# v2.net
KiCad netlist of a schematic drawn in EAGLE
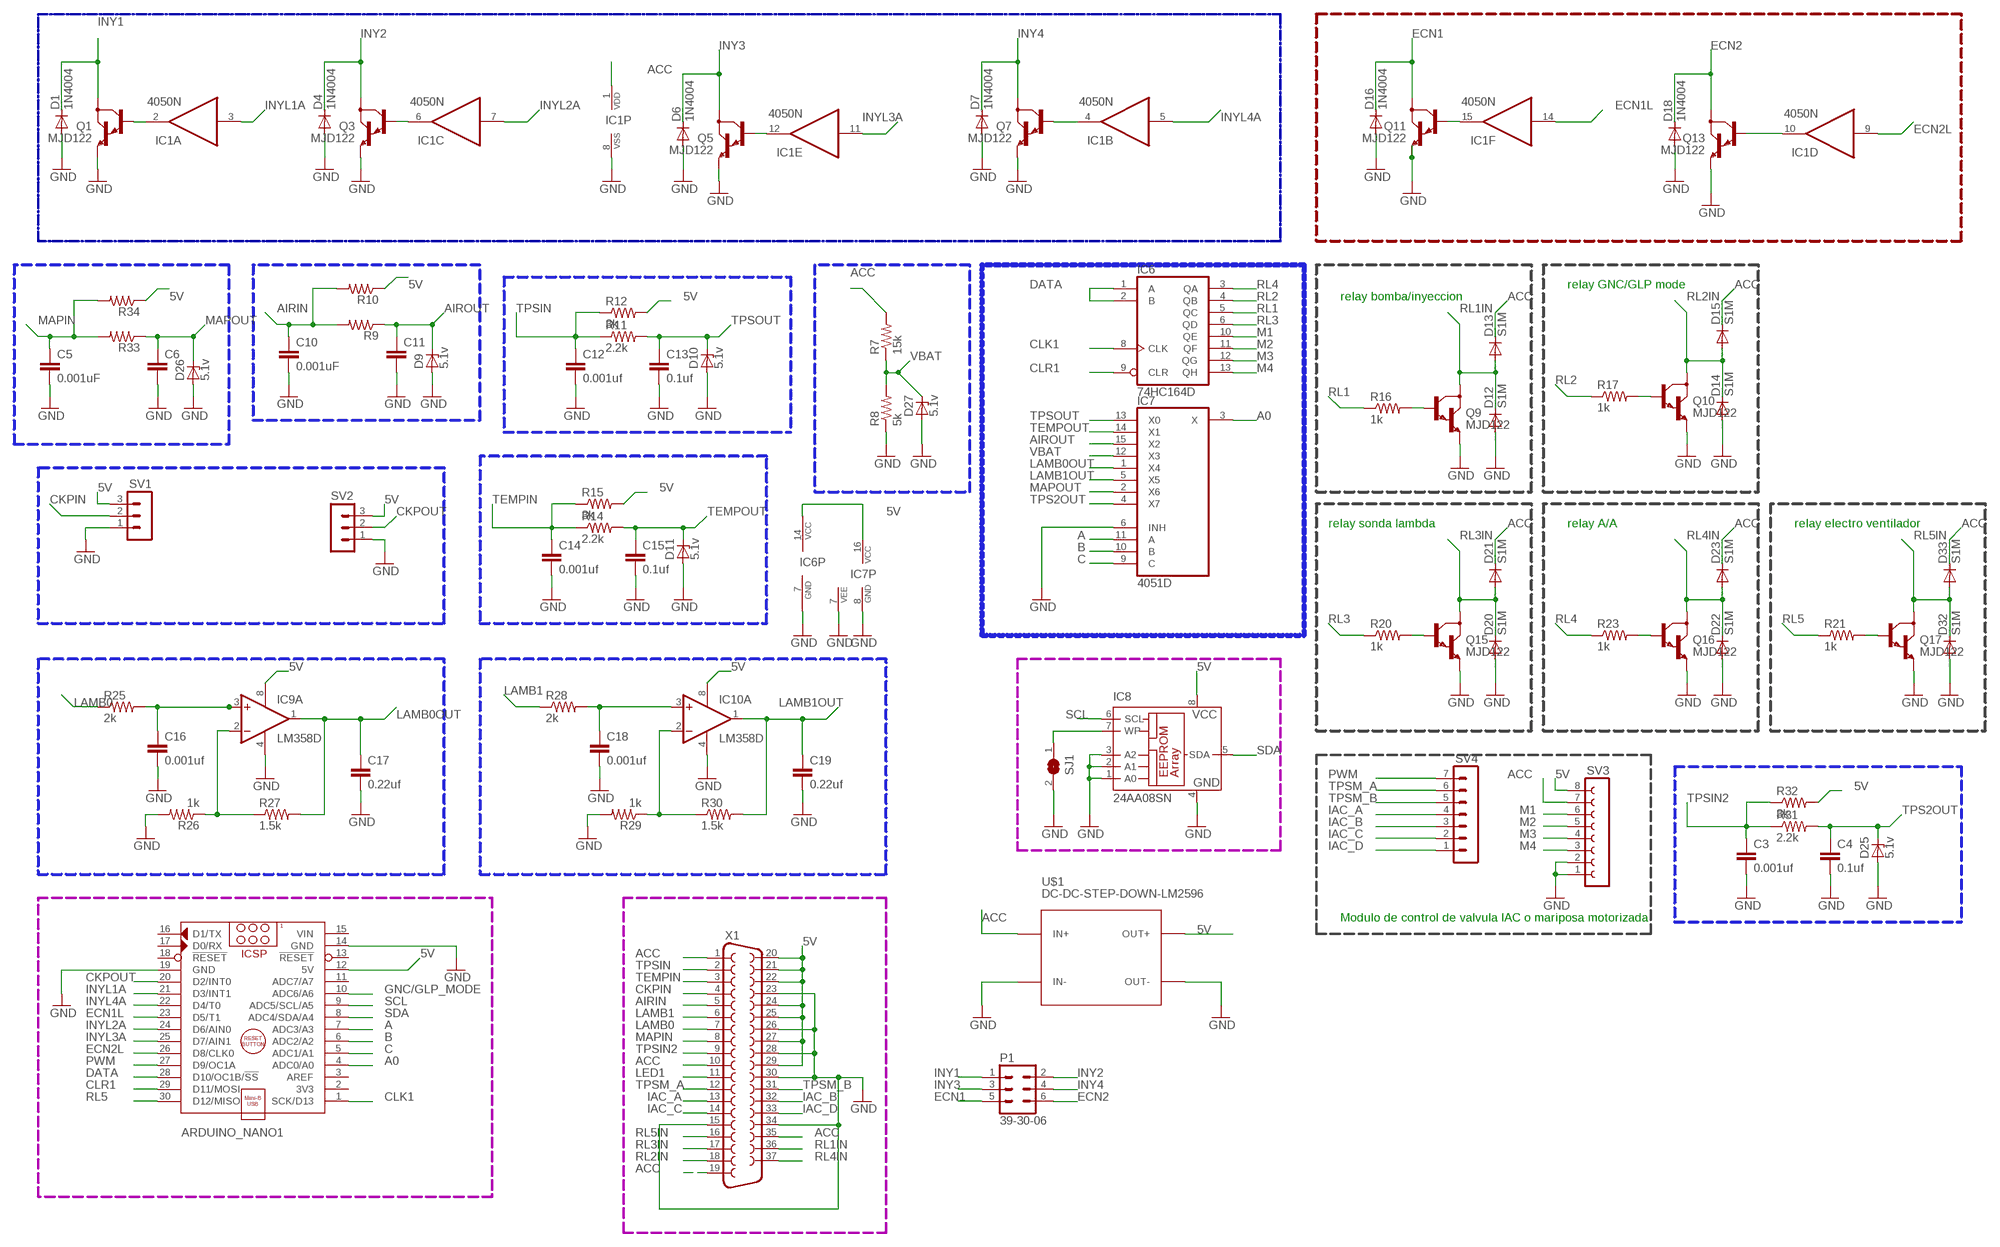
[diagram p0: schematic, sheet 1]

(export (version "E")
  (design (tool "Eeschema 10.0.6"))
  (components
    (comp (ref "ARDUINO_NANO1")
      (value "ARDUINO_NANO")
      (footprint "eagle-import:ARDUINO_NANO")
      (libsource (lib "eagle-import") (part "ARDUINO_NANO"))
    )
    (comp (ref "C3")
      (value "0.001uf")
      (footprint "eagle-import:C025-025X050")
      (libsource (lib "eagle-import") (part "C-EU025-025X050"))
    )
    (comp (ref "C4")
      (value "0.1uf")
      (footprint "eagle-import:C025-025X050")
      (libsource (lib "eagle-import") (part "C-EU025-025X050"))
    )
    (comp (ref "C5")
      (value "0.001uF")
      (footprint "eagle-import:C025-025X050")
      (libsource (lib "eagle-import") (part "C-EU025-025X050"))
    )
    (comp (ref "C6")
      (value "C-EU025-025X050")
      (footprint "eagle-import:C025-025X050")
      (libsource (lib "eagle-import") (part "C-EU025-025X050"))
    )
    (comp (ref "C10")
      (value "0.001uF")
      (footprint "eagle-import:C025-025X050")
      (libsource (lib "eagle-import") (part "C-EU025-025X050"))
    )
    (comp (ref "C11")
      (value "C-EU025-025X050")
      (footprint "eagle-import:C025-025X050")
      (libsource (lib "eagle-import") (part "C-EU025-025X050"))
    )
    (comp (ref "C12")
      (value "0.001uf")
      (footprint "eagle-import:C025-025X050")
      (libsource (lib "eagle-import") (part "C-EU025-025X050"))
    )
    (comp (ref "C13")
      (value "0.1uf")
      (footprint "eagle-import:C025-025X050")
      (libsource (lib "eagle-import") (part "C-EU025-025X050"))
    )
    (comp (ref "C14")
      (value "0.001uf")
      (footprint "eagle-import:C025-025X050")
      (libsource (lib "eagle-import") (part "C-EU025-025X050"))
    )
    (comp (ref "C15")
      (value "0.1uf")
      (footprint "eagle-import:C025-025X050")
      (libsource (lib "eagle-import") (part "C-EU025-025X050"))
    )
    (comp (ref "C16")
      (value "0.001uf")
      (footprint "eagle-import:C025-025X050")
      (libsource (lib "eagle-import") (part "C-EU025-025X050"))
    )
    (comp (ref "C17")
      (value "0.22uf")
      (footprint "eagle-import:C025-025X050")
      (libsource (lib "eagle-import") (part "C-EU025-025X050"))
    )
    (comp (ref "C18")
      (value "0.001uf")
      (footprint "eagle-import:C025-025X050")
      (libsource (lib "eagle-import") (part "C-EU025-025X050"))
    )
    (comp (ref "C19")
      (value "0.22uf")
      (footprint "eagle-import:C025-025X050")
      (libsource (lib "eagle-import") (part "C-EU025-025X050"))
    )
    (comp (ref "D1")
      (value "1N4004")
      (footprint "eagle-import:DO41-10")
      (libsource (lib "eagle-import") (part "1N4004"))
    )
    (comp (ref "D4")
      (value "1N4004")
      (footprint "eagle-import:DO41-10")
      (libsource (lib "eagle-import") (part "1N4004"))
    )
    (comp (ref "D6")
      (value "1N4004")
      (footprint "eagle-import:DO41-10")
      (libsource (lib "eagle-import") (part "1N4004"))
    )
    (comp (ref "D7")
      (value "1N4004")
      (footprint "eagle-import:DO41-10")
      (libsource (lib "eagle-import") (part "1N4004"))
    )
    (comp (ref "D9")
      (value "5.1v")
      (footprint "eagle-import:ZDIO-5")
      (libsource (lib "eagle-import") (part "ZENER-DIODEZD-5"))
    )
    (comp (ref "D10")
      (value "5.1v")
      (footprint "eagle-import:ZDIO-5")
      (libsource (lib "eagle-import") (part "ZENER-DIODEZD-5"))
    )
    (comp (ref "D11")
      (value "5.1v")
      (footprint "eagle-import:ZDIO-5")
      (libsource (lib "eagle-import") (part "ZENER-DIODEZD-5"))
    )
    (comp (ref "D12")
      (value "S1M")
      (footprint "eagle-import:SMA")
      (libsource (lib "eagle-import") (part "S1M"))
    )
    (comp (ref "D13")
      (value "S1M")
      (footprint "eagle-import:SMA")
      (libsource (lib "eagle-import") (part "S1M"))
    )
    (comp (ref "D14")
      (value "S1M")
      (footprint "eagle-import:SMA")
      (libsource (lib "eagle-import") (part "S1M"))
    )
    (comp (ref "D15")
      (value "S1M")
      (footprint "eagle-import:SMA")
      (libsource (lib "eagle-import") (part "S1M"))
    )
    (comp (ref "D16")
      (value "1N4004")
      (footprint "eagle-import:DO41-10")
      (libsource (lib "eagle-import") (part "1N4004"))
    )
    (comp (ref "D18")
      (value "1N4004")
      (footprint "eagle-import:DO41-10")
      (libsource (lib "eagle-import") (part "1N4004"))
    )
    (comp (ref "D20")
      (value "S1M")
      (footprint "eagle-import:SMA")
      (libsource (lib "eagle-import") (part "S1M"))
    )
    (comp (ref "D21")
      (value "S1M")
      (footprint "eagle-import:SMA")
      (libsource (lib "eagle-import") (part "S1M"))
    )
    (comp (ref "D22")
      (value "S1M")
      (footprint "eagle-import:SMA")
      (libsource (lib "eagle-import") (part "S1M"))
    )
    (comp (ref "D23")
      (value "S1M")
      (footprint "eagle-import:SMA")
      (libsource (lib "eagle-import") (part "S1M"))
    )
    (comp (ref "D25")
      (value "5.1v")
      (footprint "eagle-import:ZDIO-5")
      (libsource (lib "eagle-import") (part "ZENER-DIODEZD-5"))
    )
    (comp (ref "D26")
      (value "5.1v")
      (footprint "eagle-import:ZDIO-5")
      (libsource (lib "eagle-import") (part "ZENER-DIODEZD-5"))
    )
    (comp (ref "D27")
      (value "5.1v")
      (footprint "eagle-import:ZDIO-5")
      (libsource (lib "eagle-import") (part "ZENER-DIODEZD-5"))
    )
    (comp (ref "D32")
      (value "S1M")
      (footprint "eagle-import:SMA")
      (libsource (lib "eagle-import") (part "S1M"))
    )
    (comp (ref "D33")
      (value "S1M")
      (footprint "eagle-import:SMA")
      (libsource (lib "eagle-import") (part "S1M"))
    )
    (comp (ref "IC1")
      (value "4050N")
      (footprint "eagle-import:DIL16")
      (libsource (lib "eagle-import") (part "4050N"))
    )
    (comp (ref "IC6")
      (value "74HC164D")
      (footprint "eagle-import:SO14")
      (libsource (lib "eagle-import") (part "74164DHC"))
    )
    (comp (ref "IC7")
      (value "4051D")
      (footprint "eagle-import:SO16")
      (libsource (lib "eagle-import") (part "4051D"))
    )
    (comp (ref "IC8")
      (value "24AA08SN")
      (footprint "eagle-import:SO-08")
      (fields (field (name "MF") "MICROCHIP") (field (name "MPN") "24AA08-I/SN"))
      (libsource (lib "eagle-import") (part "24SNAA08"))
    )
    (comp (ref "IC9")
      (value "LM358D")
      (footprint "eagle-import:SO08")
      (libsource (lib "eagle-import") (part "LM358D"))
    )
    (comp (ref "IC10")
      (value "LM358D")
      (footprint "eagle-import:SO08")
      (libsource (lib "eagle-import") (part "LM358D"))
    )
    (comp (ref "P1")
      (value "39-30-06")
      (footprint "eagle-import:39-30-_06_")
      (libsource (lib "eagle-import") (part "39-30-?06?"))
    )
    (comp (ref "Q1")
      (value "MJD122")
      (footprint "eagle-import:DPAK")
      (fields (field (name "MF") "STMicroelectronics"))
      (libsource (lib "eagle-import") (part "MJD122"))
    )
    (comp (ref "Q3")
      (value "MJD122")
      (footprint "eagle-import:DPAK")
      (fields (field (name "MF") "STMicroelectronics"))
      (libsource (lib "eagle-import") (part "MJD122"))
    )
    (comp (ref "Q5")
      (value "MJD122")
      (footprint "eagle-import:DPAK")
      (fields (field (name "MF") "STMicroelectronics"))
      (libsource (lib "eagle-import") (part "MJD122"))
    )
    (comp (ref "Q7")
      (value "MJD122")
      (footprint "eagle-import:DPAK")
      (fields (field (name "MF") "STMicroelectronics"))
      (libsource (lib "eagle-import") (part "MJD122"))
    )
    (comp (ref "Q9")
      (value "MJD122")
      (footprint "eagle-import:DPAK")
      (fields (field (name "MF") "STMicroelectronics"))
      (libsource (lib "eagle-import") (part "MJD122"))
    )
    (comp (ref "Q10")
      (value "MJD122")
      (footprint "eagle-import:DPAK")
      (fields (field (name "MF") "STMicroelectronics"))
      (libsource (lib "eagle-import") (part "MJD122"))
    )
    (comp (ref "Q11")
      (value "MJD122")
      (footprint "eagle-import:DPAK")
      (fields (field (name "MF") "STMicroelectronics"))
      (libsource (lib "eagle-import") (part "MJD122"))
    )
    (comp (ref "Q13")
      (value "MJD122")
      (footprint "eagle-import:DPAK")
      (fields (field (name "MF") "STMicroelectronics"))
      (libsource (lib "eagle-import") (part "MJD122"))
    )
    (comp (ref "Q15")
      (value "MJD122")
      (footprint "eagle-import:DPAK")
      (fields (field (name "MF") "STMicroelectronics"))
      (libsource (lib "eagle-import") (part "MJD122"))
    )
    (comp (ref "Q16")
      (value "MJD122")
      (footprint "eagle-import:DPAK")
      (fields (field (name "MF") "STMicroelectronics"))
      (libsource (lib "eagle-import") (part "MJD122"))
    )
    (comp (ref "Q17")
      (value "MJD122")
      (footprint "eagle-import:DPAK")
      (fields (field (name "MF") "STMicroelectronics"))
      (libsource (lib "eagle-import") (part "MJD122"))
    )
    (comp (ref "R7")
      (value "15k")
      (footprint "eagle-import:0204_5")
      (libsource (lib "eagle-import") (part "R-US_0204/5"))
    )
    (comp (ref "R8")
      (value "5k")
      (footprint "eagle-import:0204_5")
      (libsource (lib "eagle-import") (part "R-US_0204/5"))
    )
    (comp (ref "R9")
      (value "R-US_0204/5")
      (footprint "eagle-import:0204_5")
      (libsource (lib "eagle-import") (part "R-US_0204/5"))
    )
    (comp (ref "R10")
      (value "R-US_0204/5")
      (footprint "eagle-import:0204_5")
      (libsource (lib "eagle-import") (part "R-US_0204/5"))
    )
    (comp (ref "R11")
      (value "2.2k")
      (footprint "eagle-import:0204_5")
      (libsource (lib "eagle-import") (part "R-US_0204/5"))
    )
    (comp (ref "R12")
      (value "3k")
      (footprint "eagle-import:0204_5")
      (libsource (lib "eagle-import") (part "R-US_0204/5"))
    )
    (comp (ref "R14")
      (value "2.2k")
      (footprint "eagle-import:0204_5")
      (libsource (lib "eagle-import") (part "R-US_0204/5"))
    )
    (comp (ref "R15")
      (value "3k")
      (footprint "eagle-import:0204_5")
      (libsource (lib "eagle-import") (part "R-US_0204/5"))
    )
    (comp (ref "R16")
      (value "1k")
      (footprint "eagle-import:0204_5")
      (libsource (lib "eagle-import") (part "R-US_0204/5"))
    )
    (comp (ref "R17")
      (value "1k")
      (footprint "eagle-import:0204_5")
      (libsource (lib "eagle-import") (part "R-US_0204/5"))
    )
    (comp (ref "R20")
      (value "1k")
      (footprint "eagle-import:0204_5")
      (libsource (lib "eagle-import") (part "R-US_0204/5"))
    )
    (comp (ref "R21")
      (value "1k")
      (footprint "eagle-import:0204_5")
      (libsource (lib "eagle-import") (part "R-US_0204/5"))
    )
    (comp (ref "R23")
      (value "1k")
      (footprint "eagle-import:0204_5")
      (libsource (lib "eagle-import") (part "R-US_0204/5"))
    )
    (comp (ref "R25")
      (value "2k")
      (footprint "eagle-import:0204_5")
      (libsource (lib "eagle-import") (part "R-US_0204/5"))
    )
    (comp (ref "R26")
      (value "1k")
      (footprint "eagle-import:0204_5")
      (libsource (lib "eagle-import") (part "R-US_0204/5"))
    )
    (comp (ref "R27")
      (value "1.5k")
      (footprint "eagle-import:0204_5")
      (libsource (lib "eagle-import") (part "R-US_0204/5"))
    )
    (comp (ref "R28")
      (value "2k")
      (footprint "eagle-import:0204_5")
      (libsource (lib "eagle-import") (part "R-US_0204/5"))
    )
    (comp (ref "R29")
      (value "1k")
      (footprint "eagle-import:0204_5")
      (libsource (lib "eagle-import") (part "R-US_0204/5"))
    )
    (comp (ref "R30")
      (value "1.5k")
      (footprint "eagle-import:0204_5")
      (libsource (lib "eagle-import") (part "R-US_0204/5"))
    )
    (comp (ref "R31")
      (value "2.2k")
      (footprint "eagle-import:0204_5")
      (libsource (lib "eagle-import") (part "R-US_0204/5"))
    )
    (comp (ref "R32")
      (value "3k")
      (footprint "eagle-import:0204_5")
      (libsource (lib "eagle-import") (part "R-US_0204/5"))
    )
    (comp (ref "R33")
      (value "R-US_0204/5")
      (footprint "eagle-import:0204_5")
      (libsource (lib "eagle-import") (part "R-US_0204/5"))
    )
    (comp (ref "R34")
      (value "R-US_0204/5")
      (footprint "eagle-import:0204_5")
      (libsource (lib "eagle-import") (part "R-US_0204/5"))
    )
    (comp (ref "SJ1")
      (value "SJW")
      (footprint "eagle-import:SJW")
      (libsource (lib "eagle-import") (part "SJW"))
    )
    (comp (ref "SV1")
      (value "MA03-1")
      (footprint "eagle-import:MA03-1")
      (libsource (lib "eagle-import") (part "MA03-1"))
    )
    (comp (ref "SV2")
      (value "MA03-1")
      (footprint "eagle-import:MA03-1")
      (libsource (lib "eagle-import") (part "MA03-1"))
    )
    (comp (ref "SV3")
      (value "FE08-1")
      (footprint "eagle-import:FE08")
      (libsource (lib "eagle-import") (part "FE08-1"))
    )
    (comp (ref "SV4")
      (value "MA07-1")
      (footprint "eagle-import:MA07-1")
      (libsource (lib "eagle-import") (part "MA07-1"))
    )
    (comp (ref "U$1")
      (value "DC-DC-STEP-DOWN-LM2596")
      (footprint "eagle-import:DC-DC-STEP-DOWN-LM2596")
      (libsource (lib "eagle-import") (part "DC-DC-STEP-DOWN-LM2596"))
    )
    (comp (ref "X1")
      (value "F37HP")
      (footprint "eagle-import:F37HP")
      (libsource (lib "eagle-import") (part "F37HP"))
    )
  )
  (nets
    (net (code "1") (name "/5V") (class "Default")
      (node (ref "ARDUINO_NANO1") (pin "12") (pinfunction "5V_12") (pintype "power_in"))
      (node (ref "IC10") (pin "8") (pinfunction "V+_8") (pintype "power_in"))
      (node (ref "IC6") (pin "14") (pinfunction "VCC_14") (pintype "power_in"))
      (node (ref "IC7") (pin "16") (pinfunction "VCC_16") (pintype "power_in"))
      (node (ref "IC8") (pin "8") (pinfunction "VCC_8") (pintype "power_in"))
      (node (ref "IC9") (pin "8") (pinfunction "V+_8") (pintype "power_in"))
      (node (ref "R10") (pin "1") (pinfunction "1_1") (pintype "passive"))
      (node (ref "R12") (pin "2") (pinfunction "2_2") (pintype "passive"))
      (node (ref "R15") (pin "2") (pinfunction "2_2") (pintype "passive"))
      (node (ref "R32") (pin "2") (pinfunction "2_2") (pintype "passive"))
      (node (ref "R34") (pin "1") (pinfunction "1_1") (pintype "passive"))
      (node (ref "SV1") (pin "3") (pinfunction "3_3") (pintype "passive"))
      (node (ref "SV2") (pin "3") (pinfunction "3_3") (pintype "passive"))
      (node (ref "SV3") (pin "8") (pinfunction "8_8") (pintype "passive"))
      (node (ref "U$1") (pin "OUT+") (pinfunction "OUT+_OUT+") (pintype "bidirectional"))
      (node (ref "X1") (pin "20") (pinfunction "20_20") (pintype "passive"))
      (node (ref "X1") (pin "21") (pinfunction "21_21") (pintype "passive"))
      (node (ref "X1") (pin "22") (pinfunction "22_22") (pintype "passive"))
      (node (ref "X1") (pin "24") (pinfunction "24_24") (pintype "passive"))
      (node (ref "X1") (pin "25") (pinfunction "25_25") (pintype "passive"))
      (node (ref "X1") (pin "27") (pinfunction "27_27") (pintype "passive"))
      (node (ref "X1") (pin "29") (pinfunction "29_29") (pintype "passive"))
    )
    (net (code "2") (name "/A") (class "Default")
      (node (ref "ARDUINO_NANO1") (pin "7") (pinfunction "ADC3/A3_7") (pintype "bidirectional"))
      (node (ref "IC7") (pin "11") (pinfunction "A_11") (pintype "input"))
    )
    (net (code "3") (name "/A0") (class "Default")
      (node (ref "ARDUINO_NANO1") (pin "4") (pinfunction "ADC0/A0_4") (pintype "bidirectional"))
      (node (ref "IC7") (pin "3") (pinfunction "X_3") (pintype "bidirectional"))
    )
    (net (code "4") (name "/ACC") (class "Default")
      (node (ref "D13") (pin "C") (pinfunction "C_C") (pintype "passive"))
      (node (ref "D15") (pin "C") (pinfunction "C_C") (pintype "passive"))
      (node (ref "D21") (pin "C") (pinfunction "C_C") (pintype "passive"))
      (node (ref "D23") (pin "C") (pinfunction "C_C") (pintype "passive"))
      (node (ref "D33") (pin "C") (pinfunction "C_C") (pintype "passive"))
      (node (ref "IC1") (pin "1") (pinfunction "VDD_1") (pintype "power_in"))
      (node (ref "R7") (pin "2") (pinfunction "2_2") (pintype "passive"))
      (node (ref "SV3") (pin "7") (pinfunction "7_7") (pintype "passive"))
      (node (ref "U$1") (pin "IN+") (pinfunction "IN+_IN+") (pintype "bidirectional"))
      (node (ref "X1") (pin "1") (pinfunction "1_1") (pintype "passive"))
      (node (ref "X1") (pin "10") (pinfunction "10_10") (pintype "passive"))
      (node (ref "X1") (pin "19") (pinfunction "19_19") (pintype "passive"))
      (node (ref "X1") (pin "35") (pinfunction "35_35") (pintype "passive"))
    )
    (net (code "5") (name "/AIRIN") (class "Default")
      (node (ref "C10") (pin "1") (pinfunction "1_1") (pintype "passive"))
      (node (ref "R10") (pin "2") (pinfunction "2_2") (pintype "passive"))
      (node (ref "R9") (pin "2") (pinfunction "2_2") (pintype "passive"))
      (node (ref "X1") (pin "5") (pinfunction "5_5") (pintype "passive"))
    )
    (net (code "6") (name "/AIROUT") (class "Default")
      (node (ref "C11") (pin "1") (pinfunction "1_1") (pintype "passive"))
      (node (ref "D9") (pin "C") (pinfunction "C_C") (pintype "passive"))
      (node (ref "IC7") (pin "15") (pinfunction "X2_15") (pintype "bidirectional"))
      (node (ref "R9") (pin "1") (pinfunction "1_1") (pintype "passive"))
    )
    (net (code "7") (name "/B") (class "Default")
      (node (ref "ARDUINO_NANO1") (pin "6") (pinfunction "ADC2/A2_6") (pintype "bidirectional"))
      (node (ref "IC7") (pin "10") (pinfunction "B_10") (pintype "input"))
    )
    (net (code "8") (name "/C") (class "Default")
      (node (ref "ARDUINO_NANO1") (pin "5") (pinfunction "ADC1/A1_5") (pintype "bidirectional"))
      (node (ref "IC7") (pin "9") (pinfunction "C_9") (pintype "input"))
    )
    (net (code "9") (name "/CKPIN") (class "Default")
      (node (ref "SV1") (pin "2") (pinfunction "2_2") (pintype "passive"))
      (node (ref "X1") (pin "4") (pinfunction "4_4") (pintype "passive"))
    )
    (net (code "10") (name "/CKPOUT") (class "Default")
      (node (ref "ARDUINO_NANO1") (pin "20") (pinfunction "D2/INT0_20") (pintype "bidirectional"))
      (node (ref "SV2") (pin "2") (pinfunction "2_2") (pintype "passive"))
    )
    (net (code "11") (name "/CLK1") (class "Default")
      (node (ref "ARDUINO_NANO1") (pin "1") (pinfunction "SCK/D13_1") (pintype "bidirectional"))
      (node (ref "IC6") (pin "8") (pinfunction "CLK_8") (pintype "input"))
    )
    (net (code "12") (name "/CLR1") (class "Default")
      (node (ref "ARDUINO_NANO1") (pin "29") (pinfunction "D11/MOSI_29") (pintype "bidirectional"))
      (node (ref "IC6") (pin "9") (pinfunction "CLR_9") (pintype "input"))
    )
    (net (code "13") (name "/DATA") (class "Default")
      (node (ref "ARDUINO_NANO1") (pin "28") (pinfunction "D10/OC1B/~{SS}_28") (pintype "bidirectional"))
      (node (ref "IC6") (pin "1") (pinfunction "A_1") (pintype "input"))
      (node (ref "IC6") (pin "2") (pinfunction "B_2") (pintype "input"))
    )
    (net (code "14") (name "/ECN1") (class "Default")
      (node (ref "D16") (pin "C") (pinfunction "C_C") (pintype "passive"))
      (node (ref "P1") (pin "5") (pinfunction "5_5") (pintype "passive"))
      (node (ref "Q11") (pin "4") (pinfunction "C_4") (pintype "passive"))
    )
    (net (code "15") (name "/ECN1L") (class "Default")
      (node (ref "ARDUINO_NANO1") (pin "23") (pinfunction "D5/T1_23") (pintype "bidirectional"))
      (node (ref "IC1") (pin "14") (pinfunction "I_14") (pintype "input"))
    )
    (net (code "16") (name "/ECN2") (class "Default")
      (node (ref "D18") (pin "C") (pinfunction "C_C") (pintype "passive"))
      (node (ref "P1") (pin "6") (pinfunction "6_6") (pintype "passive"))
      (node (ref "Q13") (pin "4") (pinfunction "C_4") (pintype "passive"))
    )
    (net (code "17") (name "/ECN2L") (class "Default")
      (node (ref "ARDUINO_NANO1") (pin "26") (pinfunction "D8/CLK0_26") (pintype "bidirectional"))
      (node (ref "IC1") (pin "9") (pinfunction "I_9") (pintype "input"))
    )
    (net (code "18") (name "/GNC{slash}GLP_MODE") (class "Default")
      (node (ref "ARDUINO_NANO1") (pin "10") (pinfunction "ADC6/A6_10") (pintype "bidirectional"))
    )
    (net (code "19") (name "/IAC_A") (class "Default")
      (node (ref "SV4") (pin "4") (pinfunction "4_4") (pintype "passive"))
      (node (ref "X1") (pin "13") (pinfunction "13_13") (pintype "passive"))
    )
    (net (code "20") (name "/IAC_B") (class "Default")
      (node (ref "SV4") (pin "3") (pinfunction "3_3") (pintype "passive"))
      (node (ref "X1") (pin "32") (pinfunction "32_32") (pintype "passive"))
    )
    (net (code "21") (name "/IAC_C") (class "Default")
      (node (ref "SV4") (pin "2") (pinfunction "2_2") (pintype "passive"))
      (node (ref "X1") (pin "14") (pinfunction "14_14") (pintype "passive"))
    )
    (net (code "22") (name "/IAC_D") (class "Default")
      (node (ref "SV4") (pin "1") (pinfunction "1_1") (pintype "passive"))
      (node (ref "X1") (pin "33") (pinfunction "33_33") (pintype "passive"))
    )
    (net (code "23") (name "/INY1") (class "Default")
      (node (ref "D1") (pin "C") (pinfunction "C_C") (pintype "passive"))
      (node (ref "P1") (pin "1") (pinfunction "1_1") (pintype "passive"))
      (node (ref "Q1") (pin "4") (pinfunction "C_4") (pintype "passive"))
    )
    (net (code "24") (name "/INY2") (class "Default")
      (node (ref "D4") (pin "C") (pinfunction "C_C") (pintype "passive"))
      (node (ref "P1") (pin "2") (pinfunction "2_2") (pintype "passive"))
      (node (ref "Q3") (pin "4") (pinfunction "C_4") (pintype "passive"))
    )
    (net (code "25") (name "/INY3") (class "Default")
      (node (ref "D6") (pin "C") (pinfunction "C_C") (pintype "passive"))
      (node (ref "P1") (pin "3") (pinfunction "3_3") (pintype "passive"))
      (node (ref "Q5") (pin "4") (pinfunction "C_4") (pintype "passive"))
    )
    (net (code "26") (name "/INY4") (class "Default")
      (node (ref "D7") (pin "C") (pinfunction "C_C") (pintype "passive"))
      (node (ref "P1") (pin "4") (pinfunction "4_4") (pintype "passive"))
      (node (ref "Q7") (pin "4") (pinfunction "C_4") (pintype "passive"))
    )
    (net (code "27") (name "/INYL1A") (class "Default")
      (node (ref "ARDUINO_NANO1") (pin "21") (pinfunction "D3/INT1_21") (pintype "bidirectional"))
      (node (ref "IC1") (pin "3") (pinfunction "I_3") (pintype "input"))
    )
    (net (code "28") (name "/INYL2A") (class "Default")
      (node (ref "ARDUINO_NANO1") (pin "24") (pinfunction "D6/AIN0_24") (pintype "bidirectional"))
      (node (ref "IC1") (pin "7") (pinfunction "I_7") (pintype "input"))
    )
    (net (code "29") (name "/INYL3A") (class "Default")
      (node (ref "ARDUINO_NANO1") (pin "25") (pinfunction "D7/AIN1_25") (pintype "bidirectional"))
      (node (ref "IC1") (pin "11") (pinfunction "I_11") (pintype "input"))
    )
    (net (code "30") (name "/INYL4A") (class "Default")
      (node (ref "ARDUINO_NANO1") (pin "22") (pinfunction "D4/T0_22") (pintype "bidirectional"))
      (node (ref "IC1") (pin "5") (pinfunction "I_5") (pintype "input"))
    )
    (net (code "31") (name "/LAMB0") (class "Default")
      (node (ref "R25") (pin "1") (pinfunction "1_1") (pintype "passive"))
      (node (ref "X1") (pin "7") (pinfunction "7_7") (pintype "passive"))
    )
    (net (code "32") (name "/LAMB0OUT") (class "Default")
      (node (ref "C17") (pin "1") (pinfunction "1_1") (pintype "passive"))
      (node (ref "IC7") (pin "1") (pinfunction "X4_1") (pintype "bidirectional"))
      (node (ref "IC9") (pin "1") (pinfunction "OUT_1") (pintype "output"))
      (node (ref "R27") (pin "2") (pinfunction "2_2") (pintype "passive"))
    )
    (net (code "33") (name "/LAMB1") (class "Default")
      (node (ref "R28") (pin "1") (pinfunction "1_1") (pintype "passive"))
      (node (ref "X1") (pin "6") (pinfunction "6_6") (pintype "passive"))
    )
    (net (code "34") (name "/LAMB1OUT") (class "Default")
      (node (ref "C19") (pin "1") (pinfunction "1_1") (pintype "passive"))
      (node (ref "IC10") (pin "1") (pinfunction "OUT_1") (pintype "output"))
      (node (ref "IC7") (pin "5") (pinfunction "X5_5") (pintype "bidirectional"))
      (node (ref "R30") (pin "2") (pinfunction "2_2") (pintype "passive"))
    )
    (net (code "35") (name "/LED1") (class "Default")
      (node (ref "X1") (pin "11") (pinfunction "11_11") (pintype "passive"))
    )
    (net (code "36") (name "/M1") (class "Default")
      (node (ref "IC6") (pin "10") (pinfunction "QE_10") (pintype "output"))
      (node (ref "SV3") (pin "6") (pinfunction "6_6") (pintype "passive"))
    )
    (net (code "37") (name "/M2") (class "Default")
      (node (ref "IC6") (pin "11") (pinfunction "QF_11") (pintype "output"))
      (node (ref "SV3") (pin "5") (pinfunction "5_5") (pintype "passive"))
    )
    (net (code "38") (name "/M3") (class "Default")
      (node (ref "IC6") (pin "12") (pinfunction "QG_12") (pintype "output"))
      (node (ref "SV3") (pin "4") (pinfunction "4_4") (pintype "passive"))
    )
    (net (code "39") (name "/M4") (class "Default")
      (node (ref "IC6") (pin "13") (pinfunction "QH_13") (pintype "output"))
      (node (ref "SV3") (pin "3") (pinfunction "3_3") (pintype "passive"))
    )
    (net (code "40") (name "/MAPIN") (class "Default")
      (node (ref "C5") (pin "1") (pinfunction "1_1") (pintype "passive"))
      (node (ref "R33") (pin "2") (pinfunction "2_2") (pintype "passive"))
      (node (ref "R34") (pin "2") (pinfunction "2_2") (pintype "passive"))
      (node (ref "X1") (pin "8") (pinfunction "8_8") (pintype "passive"))
    )
    (net (code "41") (name "/MAPOUT") (class "Default")
      (node (ref "C6") (pin "1") (pinfunction "1_1") (pintype "passive"))
      (node (ref "D26") (pin "C") (pinfunction "C_C") (pintype "passive"))
      (node (ref "IC7") (pin "2") (pinfunction "X6_2") (pintype "bidirectional"))
      (node (ref "R33") (pin "1") (pinfunction "1_1") (pintype "passive"))
    )
    (net (code "42") (name "/PWM") (class "Default")
      (node (ref "ARDUINO_NANO1") (pin "27") (pinfunction "D9/OC1A_27") (pintype "bidirectional"))
      (node (ref "SV4") (pin "7") (pinfunction "7_7") (pintype "passive"))
    )
    (net (code "43") (name "/RL1") (class "Default")
      (node (ref "IC6") (pin "5") (pinfunction "QC_5") (pintype "output"))
      (node (ref "R16") (pin "1") (pinfunction "1_1") (pintype "passive"))
    )
    (net (code "44") (name "/RL1IN") (class "Default")
      (node (ref "D12") (pin "C") (pinfunction "C_C") (pintype "passive"))
      (node (ref "D13") (pin "A") (pinfunction "A_A") (pintype "passive"))
      (node (ref "Q9") (pin "4") (pinfunction "C_4") (pintype "passive"))
      (node (ref "X1") (pin "36") (pinfunction "36_36") (pintype "passive"))
    )
    (net (code "45") (name "/RL2") (class "Default")
      (node (ref "IC6") (pin "4") (pinfunction "QB_4") (pintype "output"))
      (node (ref "R17") (pin "1") (pinfunction "1_1") (pintype "passive"))
    )
    (net (code "46") (name "/RL2IN") (class "Default")
      (node (ref "D14") (pin "C") (pinfunction "C_C") (pintype "passive"))
      (node (ref "D15") (pin "A") (pinfunction "A_A") (pintype "passive"))
      (node (ref "Q10") (pin "4") (pinfunction "C_4") (pintype "passive"))
      (node (ref "X1") (pin "18") (pinfunction "18_18") (pintype "passive"))
    )
    (net (code "47") (name "/RL3") (class "Default")
      (node (ref "IC6") (pin "6") (pinfunction "QD_6") (pintype "output"))
      (node (ref "R20") (pin "1") (pinfunction "1_1") (pintype "passive"))
    )
    (net (code "48") (name "/RL3IN") (class "Default")
      (node (ref "D20") (pin "C") (pinfunction "C_C") (pintype "passive"))
      (node (ref "D21") (pin "A") (pinfunction "A_A") (pintype "passive"))
      (node (ref "Q15") (pin "4") (pinfunction "C_4") (pintype "passive"))
      (node (ref "X1") (pin "17") (pinfunction "17_17") (pintype "passive"))
    )
    (net (code "49") (name "/RL4") (class "Default")
      (node (ref "IC6") (pin "3") (pinfunction "QA_3") (pintype "output"))
      (node (ref "R23") (pin "1") (pinfunction "1_1") (pintype "passive"))
    )
    (net (code "50") (name "/RL4IN") (class "Default")
      (node (ref "D22") (pin "C") (pinfunction "C_C") (pintype "passive"))
      (node (ref "D23") (pin "A") (pinfunction "A_A") (pintype "passive"))
      (node (ref "Q16") (pin "4") (pinfunction "C_4") (pintype "passive"))
      (node (ref "X1") (pin "37") (pinfunction "37_37") (pintype "passive"))
    )
    (net (code "51") (name "/RL5") (class "Default")
      (node (ref "ARDUINO_NANO1") (pin "30") (pinfunction "D12/MISO_30") (pintype "bidirectional"))
      (node (ref "R21") (pin "1") (pinfunction "1_1") (pintype "passive"))
    )
    (net (code "52") (name "/RL5IN") (class "Default")
      (node (ref "D32") (pin "C") (pinfunction "C_C") (pintype "passive"))
      (node (ref "D33") (pin "A") (pinfunction "A_A") (pintype "passive"))
      (node (ref "Q17") (pin "4") (pinfunction "C_4") (pintype "passive"))
      (node (ref "X1") (pin "16") (pinfunction "16_16") (pintype "passive"))
    )
    (net (code "53") (name "/SCL") (class "Default")
      (node (ref "ARDUINO_NANO1") (pin "9") (pinfunction "ADC5/SCL/A5_9") (pintype "bidirectional"))
      (node (ref "IC8") (pin "6") (pinfunction "SCL_6") (pintype "input"))
    )
    (net (code "54") (name "/SDA") (class "Default")
      (node (ref "ARDUINO_NANO1") (pin "8") (pinfunction "ADC4/SDA/A4_8") (pintype "bidirectional"))
      (node (ref "IC8") (pin "5") (pinfunction "SDA_5") (pintype "bidirectional"))
    )
    (net (code "55") (name "/TEMPIN") (class "Default")
      (node (ref "C14") (pin "1") (pinfunction "1_1") (pintype "passive"))
      (node (ref "R14") (pin "1") (pinfunction "1_1") (pintype "passive"))
      (node (ref "R15") (pin "1") (pinfunction "1_1") (pintype "passive"))
      (node (ref "X1") (pin "3") (pinfunction "3_3") (pintype "passive"))
    )
    (net (code "56") (name "/TEMPOUT") (class "Default")
      (node (ref "C15") (pin "1") (pinfunction "1_1") (pintype "passive"))
      (node (ref "D11") (pin "C") (pinfunction "C_C") (pintype "passive"))
      (node (ref "IC7") (pin "14") (pinfunction "X1_14") (pintype "bidirectional"))
      (node (ref "R14") (pin "2") (pinfunction "2_2") (pintype "passive"))
    )
    (net (code "57") (name "/TPS2OUT") (class "Default")
      (node (ref "C4") (pin "1") (pinfunction "1_1") (pintype "passive"))
      (node (ref "D25") (pin "C") (pinfunction "C_C") (pintype "passive"))
      (node (ref "IC7") (pin "4") (pinfunction "X7_4") (pintype "bidirectional"))
      (node (ref "R31") (pin "2") (pinfunction "2_2") (pintype "passive"))
    )
    (net (code "58") (name "/TPSIN") (class "Default")
      (node (ref "C12") (pin "1") (pinfunction "1_1") (pintype "passive"))
      (node (ref "R11") (pin "1") (pinfunction "1_1") (pintype "passive"))
      (node (ref "R12") (pin "1") (pinfunction "1_1") (pintype "passive"))
      (node (ref "X1") (pin "2") (pinfunction "2_2") (pintype "passive"))
    )
    (net (code "59") (name "/TPSIN2") (class "Default")
      (node (ref "C3") (pin "1") (pinfunction "1_1") (pintype "passive"))
      (node (ref "R31") (pin "1") (pinfunction "1_1") (pintype "passive"))
      (node (ref "R32") (pin "1") (pinfunction "1_1") (pintype "passive"))
      (node (ref "X1") (pin "9") (pinfunction "9_9") (pintype "passive"))
    )
    (net (code "60") (name "/TPSM_A") (class "Default")
      (node (ref "SV4") (pin "6") (pinfunction "6_6") (pintype "passive"))
      (node (ref "X1") (pin "12") (pinfunction "12_12") (pintype "passive"))
    )
    (net (code "61") (name "/TPSM_B") (class "Default")
      (node (ref "SV4") (pin "5") (pinfunction "5_5") (pintype "passive"))
      (node (ref "X1") (pin "31") (pinfunction "31_31") (pintype "passive"))
    )
    (net (code "62") (name "/TPSOUT") (class "Default")
      (node (ref "C13") (pin "1") (pinfunction "1_1") (pintype "passive"))
      (node (ref "D10") (pin "C") (pinfunction "C_C") (pintype "passive"))
      (node (ref "IC7") (pin "13") (pinfunction "X0_13") (pintype "bidirectional"))
      (node (ref "R11") (pin "2") (pinfunction "2_2") (pintype "passive"))
    )
    (net (code "63") (name "/VBAT") (class "Default")
      (node (ref "D27") (pin "C") (pinfunction "C_C") (pintype "passive"))
      (node (ref "IC7") (pin "12") (pinfunction "X3_12") (pintype "bidirectional"))
      (node (ref "R7") (pin "1") (pinfunction "1_1") (pintype "passive"))
      (node (ref "R8") (pin "2") (pinfunction "2_2") (pintype "passive"))
    )
    (net (code "64") (name "/VIN") (class "Default")
      (node (ref "ARDUINO_NANO1") (pin "15") (pinfunction "VIN_15") (pintype "power_in"))
    )
    (net (code "65") (name "GND") (class "Default")
      (node (ref "ARDUINO_NANO1") (pin "14") (pinfunction "GND_14") (pintype "power_in"))
      (node (ref "ARDUINO_NANO1") (pin "19") (pinfunction "GND_19") (pintype "power_in"))
      (node (ref "C10") (pin "2") (pinfunction "2_2") (pintype "passive"))
      (node (ref "C11") (pin "2") (pinfunction "2_2") (pintype "passive"))
      (node (ref "C12") (pin "2") (pinfunction "2_2") (pintype "passive"))
      (node (ref "C13") (pin "2") (pinfunction "2_2") (pintype "passive"))
      (node (ref "C14") (pin "2") (pinfunction "2_2") (pintype "passive"))
      (node (ref "C15") (pin "2") (pinfunction "2_2") (pintype "passive"))
      (node (ref "C16") (pin "2") (pinfunction "2_2") (pintype "passive"))
      (node (ref "C17") (pin "2") (pinfunction "2_2") (pintype "passive"))
      (node (ref "C18") (pin "2") (pinfunction "2_2") (pintype "passive"))
      (node (ref "C19") (pin "2") (pinfunction "2_2") (pintype "passive"))
      (node (ref "C3") (pin "2") (pinfunction "2_2") (pintype "passive"))
      (node (ref "C4") (pin "2") (pinfunction "2_2") (pintype "passive"))
      (node (ref "C5") (pin "2") (pinfunction "2_2") (pintype "passive"))
      (node (ref "C6") (pin "2") (pinfunction "2_2") (pintype "passive"))
      (node (ref "D1") (pin "A") (pinfunction "A_A") (pintype "passive"))
      (node (ref "D10") (pin "A") (pinfunction "A_A") (pintype "passive"))
      (node (ref "D11") (pin "A") (pinfunction "A_A") (pintype "passive"))
      (node (ref "D12") (pin "A") (pinfunction "A_A") (pintype "passive"))
      (node (ref "D14") (pin "A") (pinfunction "A_A") (pintype "passive"))
      (node (ref "D16") (pin "A") (pinfunction "A_A") (pintype "passive"))
      (node (ref "D18") (pin "A") (pinfunction "A_A") (pintype "passive"))
      (node (ref "D20") (pin "A") (pinfunction "A_A") (pintype "passive"))
      (node (ref "D22") (pin "A") (pinfunction "A_A") (pintype "passive"))
      (node (ref "D25") (pin "A") (pinfunction "A_A") (pintype "passive"))
      (node (ref "D26") (pin "A") (pinfunction "A_A") (pintype "passive"))
      (node (ref "D27") (pin "A") (pinfunction "A_A") (pintype "passive"))
      (node (ref "D32") (pin "A") (pinfunction "A_A") (pintype "passive"))
      (node (ref "D4") (pin "A") (pinfunction "A_A") (pintype "passive"))
      (node (ref "D6") (pin "A") (pinfunction "A_A") (pintype "passive"))
      (node (ref "D7") (pin "A") (pinfunction "A_A") (pintype "passive"))
      (node (ref "D9") (pin "A") (pinfunction "A_A") (pintype "passive"))
      (node (ref "IC1") (pin "8") (pinfunction "VSS_8") (pintype "power_in"))
      (node (ref "IC10") (pin "4") (pinfunction "V-_4") (pintype "power_in"))
      (node (ref "IC6") (pin "7") (pinfunction "GND_7") (pintype "power_in"))
      (node (ref "IC7") (pin "6") (pinfunction "INH_6") (pintype "input"))
      (node (ref "IC7") (pin "7") (pinfunction "VEE_7") (pintype "power_in"))
      (node (ref "IC7") (pin "8") (pinfunction "GND_8") (pintype "power_in"))
      (node (ref "IC8") (pin "1") (pinfunction "A0_1") (pintype "input"))
      (node (ref "IC8") (pin "2") (pinfunction "A1_2") (pintype "input"))
      (node (ref "IC8") (pin "3") (pinfunction "A2_3") (pintype "input"))
      (node (ref "IC8") (pin "4") (pinfunction "GND_4") (pintype "power_in"))
      (node (ref "IC9") (pin "4") (pinfunction "V-_4") (pintype "power_in"))
      (node (ref "Q1") (pin "3") (pinfunction "E_3") (pintype "passive"))
      (node (ref "Q10") (pin "3") (pinfunction "E_3") (pintype "passive"))
      (node (ref "Q11") (pin "3") (pinfunction "E_3") (pintype "passive"))
      (node (ref "Q13") (pin "3") (pinfunction "E_3") (pintype "passive"))
      (node (ref "Q15") (pin "3") (pinfunction "E_3") (pintype "passive"))
      (node (ref "Q16") (pin "3") (pinfunction "E_3") (pintype "passive"))
      (node (ref "Q17") (pin "3") (pinfunction "E_3") (pintype "passive"))
      (node (ref "Q3") (pin "3") (pinfunction "E_3") (pintype "passive"))
      (node (ref "Q5") (pin "3") (pinfunction "E_3") (pintype "passive"))
      (node (ref "Q7") (pin "3") (pinfunction "E_3") (pintype "passive"))
      (node (ref "Q9") (pin "3") (pinfunction "E_3") (pintype "passive"))
      (node (ref "R26") (pin "2") (pinfunction "2_2") (pintype "passive"))
      (node (ref "R29") (pin "2") (pinfunction "2_2") (pintype "passive"))
      (node (ref "R8") (pin "1") (pinfunction "1_1") (pintype "passive"))
      (node (ref "SJ1") (pin "2") (pinfunction "2_2") (pintype "passive"))
      (node (ref "SV1") (pin "1") (pinfunction "1_1") (pintype "passive"))
      (node (ref "SV2") (pin "1") (pinfunction "1_1") (pintype "passive"))
      (node (ref "SV3") (pin "1") (pinfunction "1_1") (pintype "passive"))
      (node (ref "SV3") (pin "2") (pinfunction "2_2") (pintype "passive"))
      (node (ref "U$1") (pin "IN-") (pinfunction "IN-_IN-") (pintype "bidirectional"))
      (node (ref "U$1") (pin "OUT-") (pinfunction "OUT-_OUT-") (pintype "bidirectional"))
      (node (ref "X1") (pin "15") (pinfunction "15_15") (pintype "passive"))
      (node (ref "X1") (pin "23") (pinfunction "23_23") (pintype "passive"))
      (node (ref "X1") (pin "26") (pinfunction "26_26") (pintype "passive"))
      (node (ref "X1") (pin "28") (pinfunction "28_28") (pintype "passive"))
      (node (ref "X1") (pin "30") (pinfunction "30_30") (pintype "passive"))
      (node (ref "X1") (pin "34") (pinfunction "34_34") (pintype "passive"))
    )
    (net (code "66") (name "Net-(IC1A-O)") (class "Default")
      (node (ref "IC1") (pin "2") (pinfunction "O_2") (pintype "output"))
      (node (ref "Q1") (pin "1") (pinfunction "B_1") (pintype "passive"))
    )
    (net (code "67") (name "Net-(IC1B-O)") (class "Default")
      (node (ref "IC1") (pin "4") (pinfunction "O_4") (pintype "output"))
      (node (ref "Q7") (pin "1") (pinfunction "B_1") (pintype "passive"))
    )
    (net (code "68") (name "Net-(IC1C-O)") (class "Default")
      (node (ref "IC1") (pin "6") (pinfunction "O_6") (pintype "output"))
      (node (ref "Q3") (pin "1") (pinfunction "B_1") (pintype "passive"))
    )
    (net (code "69") (name "Net-(IC1D-O)") (class "Default")
      (node (ref "IC1") (pin "10") (pinfunction "O_10") (pintype "output"))
      (node (ref "Q13") (pin "1") (pinfunction "B_1") (pintype "passive"))
    )
    (net (code "70") (name "Net-(IC1E-O)") (class "Default")
      (node (ref "IC1") (pin "12") (pinfunction "O_12") (pintype "output"))
      (node (ref "Q5") (pin "1") (pinfunction "B_1") (pintype "passive"))
    )
    (net (code "71") (name "Net-(IC1F-O)") (class "Default")
      (node (ref "IC1") (pin "15") (pinfunction "O_15") (pintype "output"))
      (node (ref "Q11") (pin "1") (pinfunction "B_1") (pintype "passive"))
    )
    (net (code "72") (name "Net-(IC8-WP)") (class "Default")
      (node (ref "IC8") (pin "7") (pinfunction "WP_7") (pintype "input"))
      (node (ref "SJ1") (pin "1") (pinfunction "1_1") (pintype "passive"))
    )
    (net (code "73") (name "Net-(IC9A-+IN)") (class "Default")
      (node (ref "C16") (pin "1") (pinfunction "1_1") (pintype "passive"))
      (node (ref "IC9") (pin "3") (pinfunction "+IN_3") (pintype "input"))
      (node (ref "R25") (pin "2") (pinfunction "2_2") (pintype "passive"))
    )
    (net (code "74") (name "Net-(IC9A--IN)") (class "Default")
      (node (ref "IC9") (pin "2") (pinfunction "-IN_2") (pintype "input"))
      (node (ref "R26") (pin "1") (pinfunction "1_1") (pintype "passive"))
      (node (ref "R27") (pin "1") (pinfunction "1_1") (pintype "passive"))
    )
    (net (code "75") (name "Net-(IC10A-+IN)") (class "Default")
      (node (ref "C18") (pin "1") (pinfunction "1_1") (pintype "passive"))
      (node (ref "IC10") (pin "3") (pinfunction "+IN_3") (pintype "input"))
      (node (ref "R28") (pin "2") (pinfunction "2_2") (pintype "passive"))
    )
    (net (code "76") (name "Net-(IC10A--IN)") (class "Default")
      (node (ref "IC10") (pin "2") (pinfunction "-IN_2") (pintype "input"))
      (node (ref "R29") (pin "1") (pinfunction "1_1") (pintype "passive"))
      (node (ref "R30") (pin "1") (pinfunction "1_1") (pintype "passive"))
    )
    (net (code "77") (name "Net-(Q9-B)") (class "Default")
      (node (ref "Q9") (pin "1") (pinfunction "B_1") (pintype "passive"))
      (node (ref "R16") (pin "2") (pinfunction "2_2") (pintype "passive"))
    )
    (net (code "78") (name "Net-(Q10-B)") (class "Default")
      (node (ref "Q10") (pin "1") (pinfunction "B_1") (pintype "passive"))
      (node (ref "R17") (pin "2") (pinfunction "2_2") (pintype "passive"))
    )
    (net (code "79") (name "Net-(Q15-B)") (class "Default")
      (node (ref "Q15") (pin "1") (pinfunction "B_1") (pintype "passive"))
      (node (ref "R20") (pin "2") (pinfunction "2_2") (pintype "passive"))
    )
    (net (code "80") (name "Net-(Q16-B)") (class "Default")
      (node (ref "Q16") (pin "1") (pinfunction "B_1") (pintype "passive"))
      (node (ref "R23") (pin "2") (pinfunction "2_2") (pintype "passive"))
    )
    (net (code "81") (name "Net-(Q17-B)") (class "Default")
      (node (ref "Q17") (pin "1") (pinfunction "B_1") (pintype "passive"))
      (node (ref "R21") (pin "2") (pinfunction "2_2") (pintype "passive"))
    )
    (net (code "82") (name "unconnected-(ARDUINO_NANO1-3V3-Pad2)") (class "Default")
      (node (ref "ARDUINO_NANO1") (pin "2") (pinfunction "3V3_2") (pintype "output"))
    )
    (net (code "83") (name "unconnected-(ARDUINO_NANO1-ADC7{slash}A7-Pad11)") (class "Default")
      (node (ref "ARDUINO_NANO1") (pin "11") (pinfunction "ADC7/A7_11") (pintype "bidirectional"))
    )
    (net (code "84") (name "unconnected-(ARDUINO_NANO1-AREF-Pad3)") (class "Default")
      (node (ref "ARDUINO_NANO1") (pin "3") (pinfunction "AREF_3") (pintype "input"))
    )
    (net (code "85") (name "unconnected-(ARDUINO_NANO1-D0{slash}RX-Pad17)") (class "Default")
      (node (ref "ARDUINO_NANO1") (pin "17") (pinfunction "D0/RX_17") (pintype "bidirectional"))
    )
    (net (code "86") (name "unconnected-(ARDUINO_NANO1-D1{slash}TX-Pad16)") (class "Default")
      (node (ref "ARDUINO_NANO1") (pin "16") (pinfunction "D1/TX_16") (pintype "bidirectional"))
    )
    (net (code "87") (name "unconnected-(ARDUINO_NANO1-~{RESET}-Pad13)") (class "Default")
      (node (ref "ARDUINO_NANO1") (pin "13") (pinfunction "~{RESET}_13") (pintype "input"))
    )
    (net (code "88") (name "unconnected-(ARDUINO_NANO1-~{RESET}-Pad18)") (class "Default")
      (node (ref "ARDUINO_NANO1") (pin "18") (pinfunction "~{RESET}_18") (pintype "input"))
    )
  )
)
